# picr22-team-GibiBot-mainboard.net
KiCad netlist of a schematic drawn in Altium Designer
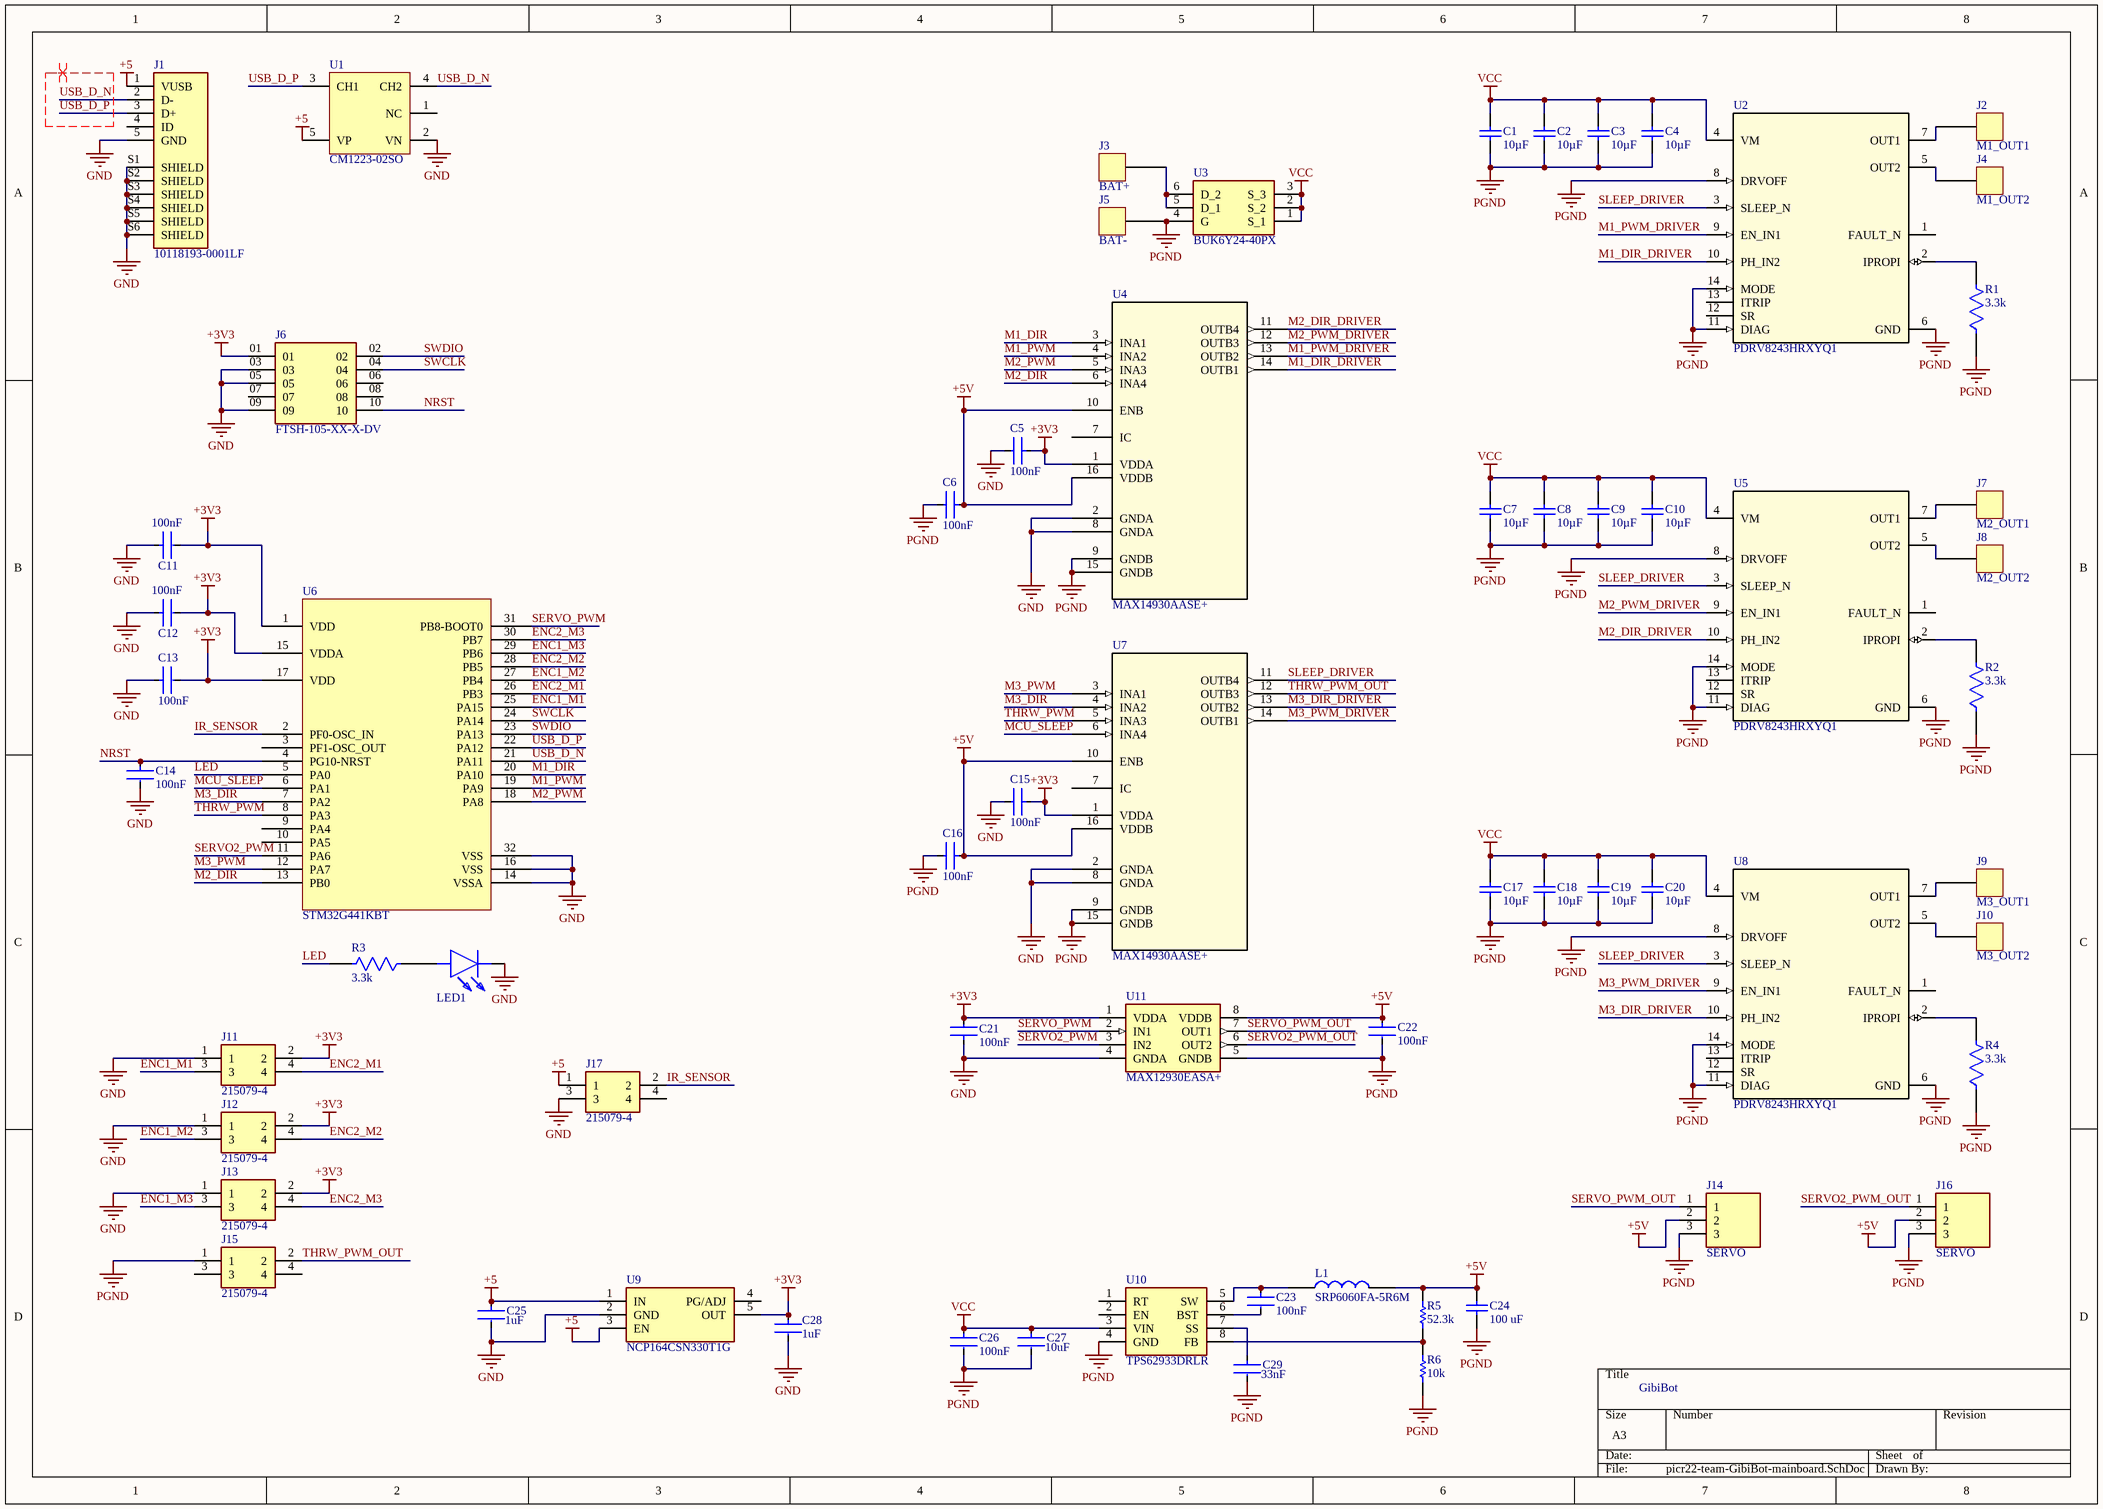
[diagram p0: picr22-team-GibiBot-mainboard.SchDoc]

(export (version "E")
  (design (tool "Eeschema 10.0.6"))
  (components
    (comp (ref "C1")
      (value "GRM21BR61A106KE19L")
      (footprint "MURA-0805_H_1.35_M")
      (description "CAP, Ceramic, 10 uF, 10%, 10 V, 0805, RoHS, Tape and Reel")
      (fields
        (field (name "MANUFACTURER") "Murata")
        (field (name "TOLERANCE") "±10%")
        (field (name "CAPACITANCE") "10µF")
      )
      (libsource (lib "Altium Content Vault") (part "CAP-NP-2"))
    )
    (comp (ref "C2")
      (value "GRM21BR61A106KE19L")
      (footprint "MURA-0805_H_1.35_M")
      (description "CAP, Ceramic, 10 uF, 10%, 10 V, 0805, RoHS, Tape and Reel")
      (fields
        (field (name "MANUFACTURER") "Murata")
        (field (name "TOLERANCE") "±10%")
        (field (name "CAPACITANCE") "10µF")
      )
      (libsource (lib "Altium Content Vault") (part "CAP-NP-2"))
    )
    (comp (ref "C3")
      (value "GRM21BR61A106KE19L")
      (footprint "MURA-0805_H_1.35_M")
      (description "CAP, Ceramic, 10 uF, 10%, 10 V, 0805, RoHS, Tape and Reel")
      (fields
        (field (name "MANUFACTURER") "Murata")
        (field (name "TOLERANCE") "±10%")
        (field (name "CAPACITANCE") "10µF")
      )
      (libsource (lib "Altium Content Vault") (part "CAP-NP-2"))
    )
    (comp (ref "C4")
      (value "GRM21BR61A106KE19L")
      (footprint "MURA-0805_H_1.35_M")
      (description "CAP, Ceramic, 10 uF, 10%, 10 V, 0805, RoHS, Tape and Reel")
      (fields
        (field (name "MANUFACTURER") "Murata")
        (field (name "TOLERANCE") "±10%")
        (field (name "CAPACITANCE") "10µF")
      )
      (libsource (lib "Altium Content Vault") (part "CAP-NP-2"))
    )
    (comp (ref "C5")
      (value "CGA3E2X7R1H104K080AA")
      (footprint "FP-CGA3E-0_3-0_1-IPC_A")
      (description "Cap Ceramic 100nF 50V X7R 10% Pad SMD 0603 +125°C Automotive T/R")
      (fields
        (field (name "TOLERANCE") "10%")
        (field (name "CAPACITANCE") "100nF")
        (field (name "VOLTAGE") "50V")
      )
      (libsource (lib "Altium Content Vault") (part "b4654b650e69147ec39a6b967a45e02"))
    )
    (comp (ref "C6")
      (value "CGA3E2X7R1H104K080AA")
      (footprint "FP-CGA3E-0_3-0_1-IPC_A")
      (description "Cap Ceramic 100nF 50V X7R 10% Pad SMD 0603 +125°C Automotive T/R")
      (fields
        (field (name "TOLERANCE") "10%")
        (field (name "CAPACITANCE") "100nF")
        (field (name "VOLTAGE") "50V")
      )
      (libsource (lib "Altium Content Vault") (part "b4654b650e69147ec39a6b967a45e02"))
    )
    (comp (ref "C7")
      (value "GRM21BR61A106KE19L")
      (footprint "MURA-0805_H_1.35_M")
      (description "CAP, Ceramic, 10 uF, 10%, 10 V, 0805, RoHS, Tape and Reel")
      (fields
        (field (name "MANUFACTURER") "Murata")
        (field (name "TOLERANCE") "±10%")
        (field (name "CAPACITANCE") "10µF")
      )
      (libsource (lib "Altium Content Vault") (part "CAP-NP-2"))
    )
    (comp (ref "C8")
      (value "GRM21BR61A106KE19L")
      (footprint "MURA-0805_H_1.35_M")
      (description "CAP, Ceramic, 10 uF, 10%, 10 V, 0805, RoHS, Tape and Reel")
      (fields
        (field (name "MANUFACTURER") "Murata")
        (field (name "TOLERANCE") "±10%")
        (field (name "CAPACITANCE") "10µF")
      )
      (libsource (lib "Altium Content Vault") (part "CAP-NP-2"))
    )
    (comp (ref "C9")
      (value "GRM21BR61A106KE19L")
      (footprint "MURA-0805_H_1.35_M")
      (description "CAP, Ceramic, 10 uF, 10%, 10 V, 0805, RoHS, Tape and Reel")
      (fields
        (field (name "MANUFACTURER") "Murata")
        (field (name "TOLERANCE") "±10%")
        (field (name "CAPACITANCE") "10µF")
      )
      (libsource (lib "Altium Content Vault") (part "CAP-NP-2"))
    )
    (comp (ref "C10")
      (value "GRM21BR61A106KE19L")
      (footprint "MURA-0805_H_1.35_M")
      (description "CAP, Ceramic, 10 uF, 10%, 10 V, 0805, RoHS, Tape and Reel")
      (fields
        (field (name "MANUFACTURER") "Murata")
        (field (name "TOLERANCE") "±10%")
        (field (name "CAPACITANCE") "10µF")
      )
      (libsource (lib "Altium Content Vault") (part "CAP-NP-2"))
    )
    (comp (ref "C11")
      (value "CGA3E2X7R1H104K080AA")
      (footprint "FP-CGA3E-0_3-0_1-IPC_A")
      (description "Cap Ceramic 100nF 50V X7R 10% Pad SMD 0603 +125°C Automotive T/R")
      (fields
        (field (name "TOLERANCE") "10%")
        (field (name "CAPACITANCE") "100nF")
        (field (name "VOLTAGE") "50V")
      )
      (libsource (lib "Altium Content Vault") (part "b4654b650e69147ec39a6b967a45e02"))
    )
    (comp (ref "C12")
      (value "CGA3E2X7R1H104K080AA")
      (footprint "FP-CGA3E-0_3-0_1-IPC_A")
      (description "Cap Ceramic 100nF 50V X7R 10% Pad SMD 0603 +125°C Automotive T/R")
      (fields
        (field (name "TOLERANCE") "10%")
        (field (name "CAPACITANCE") "100nF")
        (field (name "VOLTAGE") "50V")
      )
      (libsource (lib "Altium Content Vault") (part "b4654b650e69147ec39a6b967a45e02"))
    )
    (comp (ref "C13")
      (value "CGA3E2X7R1H104K080AA")
      (footprint "FP-CGA3E-0_3-0_1-IPC_A")
      (description "Cap Ceramic 100nF 50V X7R 10% Pad SMD 0603 +125°C Automotive T/R")
      (fields
        (field (name "TOLERANCE") "10%")
        (field (name "CAPACITANCE") "100nF")
        (field (name "VOLTAGE") "50V")
      )
      (libsource (lib "Altium Content Vault") (part "b4654b650e69147ec39a6b967a45e02"))
    )
    (comp (ref "C14")
      (value "CGA3E2X7R1H104K080AA")
      (footprint "FP-CGA3E-0_3-0_1-IPC_A")
      (description "Cap Ceramic 100nF 50V X7R 10% Pad SMD 0603 +125°C Automotive T/R")
      (fields
        (field (name "TOLERANCE") "10%")
        (field (name "CAPACITANCE") "100nF")
        (field (name "VOLTAGE") "50V")
      )
      (libsource (lib "Altium Content Vault") (part "b4654b650e69147ec39a6b967a45e02"))
    )
    (comp (ref "C15")
      (value "CGA3E2X7R1H104K080AA")
      (footprint "FP-CGA3E-0_3-0_1-IPC_A")
      (description "Cap Ceramic 100nF 50V X7R 10% Pad SMD 0603 +125°C Automotive T/R")
      (fields
        (field (name "TOLERANCE") "10%")
        (field (name "CAPACITANCE") "100nF")
        (field (name "VOLTAGE") "50V")
      )
      (libsource (lib "Altium Content Vault") (part "b4654b650e69147ec39a6b967a45e02"))
    )
    (comp (ref "C16")
      (value "CGA3E2X7R1H104K080AA")
      (footprint "FP-CGA3E-0_3-0_1-IPC_A")
      (description "Cap Ceramic 100nF 50V X7R 10% Pad SMD 0603 +125°C Automotive T/R")
      (fields
        (field (name "TOLERANCE") "10%")
        (field (name "CAPACITANCE") "100nF")
        (field (name "VOLTAGE") "50V")
      )
      (libsource (lib "Altium Content Vault") (part "b4654b650e69147ec39a6b967a45e02"))
    )
    (comp (ref "C17")
      (value "GRM21BR61A106KE19L")
      (footprint "MURA-0805_H_1.35_M")
      (description "CAP, Ceramic, 10 uF, 10%, 10 V, 0805, RoHS, Tape and Reel")
      (fields
        (field (name "MANUFACTURER") "Murata")
        (field (name "TOLERANCE") "±10%")
        (field (name "CAPACITANCE") "10µF")
      )
      (libsource (lib "Altium Content Vault") (part "CAP-NP-2"))
    )
    (comp (ref "C18")
      (value "GRM21BR61A106KE19L")
      (footprint "MURA-0805_H_1.35_M")
      (description "CAP, Ceramic, 10 uF, 10%, 10 V, 0805, RoHS, Tape and Reel")
      (fields
        (field (name "MANUFACTURER") "Murata")
        (field (name "TOLERANCE") "±10%")
        (field (name "CAPACITANCE") "10µF")
      )
      (libsource (lib "Altium Content Vault") (part "CAP-NP-2"))
    )
    (comp (ref "C19")
      (value "GRM21BR61A106KE19L")
      (footprint "MURA-0805_H_1.35_M")
      (description "CAP, Ceramic, 10 uF, 10%, 10 V, 0805, RoHS, Tape and Reel")
      (fields
        (field (name "MANUFACTURER") "Murata")
        (field (name "TOLERANCE") "±10%")
        (field (name "CAPACITANCE") "10µF")
      )
      (libsource (lib "Altium Content Vault") (part "CAP-NP-2"))
    )
    (comp (ref "C20")
      (value "GRM21BR61A106KE19L")
      (footprint "MURA-0805_H_1.35_M")
      (description "CAP, Ceramic, 10 uF, 10%, 10 V, 0805, RoHS, Tape and Reel")
      (fields
        (field (name "MANUFACTURER") "Murata")
        (field (name "TOLERANCE") "±10%")
        (field (name "CAPACITANCE") "10µF")
      )
      (libsource (lib "Altium Content Vault") (part "CAP-NP-2"))
    )
    (comp (ref "C21")
      (value "CGA3E2X7R1H104K080AA")
      (footprint "FP-CGA3E-0_3-0_1-IPC_A")
      (description "Cap Ceramic 100nF 50V X7R 10% Pad SMD 0603 +125°C Automotive T/R")
      (fields
        (field (name "TOLERANCE") "10%")
        (field (name "CAPACITANCE") "100nF")
        (field (name "VOLTAGE") "50V")
      )
      (libsource (lib "Altium Content Vault") (part "b4654b650e69147ec39a6b967a45e02"))
    )
    (comp (ref "C22")
      (value "CGA3E2X7R1H104K080AA")
      (footprint "FP-CGA3E-0_3-0_1-IPC_A")
      (description "Cap Ceramic 100nF 50V X7R 10% Pad SMD 0603 +125°C Automotive T/R")
      (fields
        (field (name "TOLERANCE") "10%")
        (field (name "CAPACITANCE") "100nF")
        (field (name "VOLTAGE") "50V")
      )
      (libsource (lib "Altium Content Vault") (part "b4654b650e69147ec39a6b967a45e02"))
    )
    (comp (ref "C23")
      (value "CGA3E2X7R1H104K080AA")
      (footprint "FP-CGA3E-0_3-0_1-IPC_A")
      (description "Cap Ceramic 100nF 50V X7R 10% Pad SMD 0603 +125°C Automotive T/R")
      (fields
        (field (name "TOLERANCE") "10%")
        (field (name "CAPACITANCE") "100nF")
        (field (name "VOLTAGE") "50V")
      )
      (libsource (lib "Altium Content Vault") (part "b4654b650e69147ec39a6b967a45e02"))
    )
    (comp (ref "C24")
      (value "GRM31CR60J107ME39L")
      (footprint "CAPC3216X190X55ML30T25")
      (description "Chip Capacitor, 100 uF, +/- 20%, 6.3 V, -55 to 85 degC, 1206 (3216 Metric), RoHS, Tape and Reel")
      (fields (field (name "TOLERANCE") "20%") (field (name "CAPACITANCE") "100 uF"))
      (libsource (lib "Altium Content Vault") (part "CAP-NP-2"))
    )
    (comp (ref "C25")
      (value "C1608X5R1C105K080AA")
      (footprint "FP-C1608-080-0_1-MFG")
      (description "Multilayer Ceramic Capacitors 1μF ±10% 16V X5R SMD 0603")
      (fields
        (field (name "CAPACITANCE") "1uF")
        (field (name "VOLTAGE") "16V")
        (field (name "TOLERANCE") "10%")
      )
      (libsource (lib "Altium Content Vault") (part "236180d848d6139a670b325ea6854c9"))
    )
    (comp (ref "C26")
      (value "CGA3E2X7R1H104K080AA")
      (footprint "FP-CGA3E-0_3-0_1-IPC_A")
      (description "Cap Ceramic 100nF 50V X7R 10% Pad SMD 0603 +125°C Automotive T/R")
      (fields
        (field (name "TOLERANCE") "10%")
        (field (name "CAPACITANCE") "100nF")
        (field (name "VOLTAGE") "50V")
      )
      (libsource (lib "Altium Content Vault") (part "b4654b650e69147ec39a6b967a45e02"))
    )
    (comp (ref "C27")
      (value "C3216X7R1V106M160AC")
      (footprint "FP-C3216-160-0_2-IPC_C")
      (description "Multilayer Ceramic Capacitors 10uF ±20% 35V X7R SMD 1206")
      (fields (field (name "TOLERANCE") "20%") (field (name "CAPACITANCE") "10uF"))
      (libsource (lib "Altium Content Vault") (part "11868f565c42a9108669ba33697ecf6"))
    )
    (comp (ref "C28")
      (value "C1608X5R1C105K080AA")
      (footprint "FP-C1608-080-0_1-MFG")
      (description "Multilayer Ceramic Capacitors 1μF ±10% 16V X5R SMD 0603")
      (fields
        (field (name "CAPACITANCE") "1uF")
        (field (name "VOLTAGE") "16V")
        (field (name "TOLERANCE") "10%")
      )
      (libsource (lib "Altium Content Vault") (part "236180d848d6139a670b325ea6854c9"))
    )
    (comp (ref "C29")
      (value "CL10B333KB8NNNC")
      (footprint "FP-CL10-IPC_B")
      (description "Cap Ceramic 33nF 50V X7R ±10% Pad SMD 0603 +125°C T/R")
      (fields
        (field (name "CAPACITANCE") "33nF")
        (field (name "VOLTAGE") "50V")
        (field (name "TOLERANCE") "10%")
      )
      (libsource (lib "Altium Content Vault") (part "b4654b650e69147ec39a6b967a45e02"))
    )
    (comp (ref "J1")
      (value "10118193-0001LF")
      (footprint "picr22-team-GibiBot-mainboard:FCI_10118193-0001LF")
      (description "USB - micro B USB 2.0 Receptacle Connector 5 Position Surface Mount, Right Angle; Through Hole")
      (fields (field (name "MF") "Amphenol ICC"))
      (libsource (lib "picr22-team-GibiBot-mainboard") (part "10118193-0001LF"))
    )
    (comp (ref "J2")
      (value "M1_OUT1")
      (footprint "Power pad")
      (libsource (lib "picr22-team-GibiBot-mainboard") (part "Power pad"))
    )
    (comp (ref "J3") (value "BAT+") (footprint "Power pad") (libsource (lib "") (part "Power pad_1")))
    (comp (ref "J4")
      (value "M1_OUT2")
      (footprint "Power pad")
      (libsource (lib "picr22-team-GibiBot-mainboard") (part "Power pad"))
    )
    (comp (ref "J5") (value "BAT-") (footprint "Power pad") (libsource (lib "") (part "Power pad_1")))
    (comp (ref "J6")
      (value "FTSH-105-XX-X-DV")
      (footprint "picr22-team-GibiBot-mainboard:SAMTEC_FTSH-105-XX-X-DV")
      (description "Connector Header Surface Mount 10 position 0.050\" (1.27mm)")
      (libsource (lib "picr22-team-GibiBot-mainboard") (part "FTSH-105-XX-X-DV"))
    )
    (comp (ref "J7")
      (value "M2_OUT1")
      (footprint "Power pad")
      (libsource (lib "picr22-team-GibiBot-mainboard") (part "Power pad"))
    )
    (comp (ref "J8")
      (value "M2_OUT2")
      (footprint "Power pad")
      (libsource (lib "picr22-team-GibiBot-mainboard") (part "Power pad"))
    )
    (comp (ref "J9")
      (value "M3_OUT1")
      (footprint "Power pad")
      (libsource (lib "picr22-team-GibiBot-mainboard") (part "Power pad"))
    )
    (comp (ref "J10")
      (value "M3_OUT2")
      (footprint "Power pad")
      (libsource (lib "picr22-team-GibiBot-mainboard") (part "Power pad"))
    )
    (comp (ref "J11")
      (value "215079-4")
      (footprint "TE_215079-4")
      (description "4 Position Receptacle Connector Through Hole")
      (fields (field (name "MF") "TE Connectivity"))
      (libsource (lib "215079-4") (part "215079-4"))
    )
    (comp (ref "J12")
      (value "215079-4")
      (footprint "TE_215079-4")
      (description "4 Position Receptacle Connector Through Hole")
      (fields (field (name "MF") "TE Connectivity"))
      (libsource (lib "215079-4") (part "215079-4"))
    )
    (comp (ref "J13")
      (value "215079-4")
      (footprint "TE_215079-4")
      (description "4 Position Receptacle Connector Through Hole")
      (fields (field (name "MF") "TE Connectivity"))
      (libsource (lib "215079-4") (part "215079-4"))
    )
    (comp (ref "J14")
      (value "SERVO")
      (footprint "picr22-team-GibiBot-mainboard:SERVO")
      (description "Connector")
      (fields
        (field (name "MOUSER PART NUMBER") "649-78208-103")
        (field (name "ARROW PART NUMBER") "78208-103")
      )
      (libsource (lib "picr22-team-GibiBot-mainboard") (part "SERVO"))
    )
    (comp (ref "J15")
      (value "215079-4")
      (footprint "TE_215079-4")
      (description "4 Position Receptacle Connector Through Hole")
      (fields (field (name "MF") "TE Connectivity"))
      (libsource (lib "215079-4") (part "215079-4"))
    )
    (comp (ref "J16")
      (value "SERVO")
      (footprint "picr22-team-GibiBot-mainboard:SERVO")
      (description "Connector")
      (fields
        (field (name "MOUSER PART NUMBER") "649-78208-103")
        (field (name "ARROW PART NUMBER") "78208-103")
      )
      (libsource (lib "picr22-team-GibiBot-mainboard") (part "SERVO"))
    )
    (comp (ref "J17")
      (value "215079-4")
      (footprint "TE_215079-4")
      (description "4 Position Receptacle Connector Through Hole")
      (fields (field (name "MF") "TE Connectivity"))
      (libsource (lib "215079-4") (part "215079-4"))
    )
    (comp (ref "L1")
      (value "SRP6060FA-5R6M")
      (footprint "SRP6060FA5R6M")
      (libsource (lib "picr22-team-GibiBot-mainboard") (part "SRP6060FA-5R6M"))
    )
    (comp (ref "LED1")
      (value "150060SS75000")
      (footprint "SamacSys:LEDC1608X80N")
      (description "LED")
      (fields (field (name "MOUSER PART NUMBER") "710-150060SS75000"))
      (libsource (lib "*") (part "150060SS75000"))
    )
    (comp (ref "R1")
      (value "CRCW06031M00FKEA")
      (footprint "FP-CRCW0603-e3-MFG")
      (description "RES Thick Film, 1MΩ, 1%, 0.1W, 100ppm/°C, 0603")
      (fields (field (name "RESISTANCE") "3.3k") (field (name "TOLERANCE") "1%"))
      (libsource (lib "Altium Content Vault") (part "1029c3af85768c4190bb7ad29bc67b5"))
    )
    (comp (ref "R2")
      (value "CRCW06031M00FKEA")
      (footprint "FP-CRCW0603-e3-MFG")
      (description "RES Thick Film, 1MΩ, 1%, 0.1W, 100ppm/°C, 0603")
      (fields (field (name "RESISTANCE") "3.3k") (field (name "TOLERANCE") "1%"))
      (libsource (lib "Altium Content Vault") (part "1029c3af85768c4190bb7ad29bc67b5"))
    )
    (comp (ref "R3")
      (value "CRCW06031M00FKEA")
      (footprint "FP-CRCW0603-e3-MFG")
      (description "RES Thick Film, 1MΩ, 1%, 0.1W, 100ppm/°C, 0603")
      (fields (field (name "RESISTANCE") "3.3k") (field (name "TOLERANCE") "1%"))
      (libsource (lib "Altium Content Vault") (part "1029c3af85768c4190bb7ad29bc67b5"))
    )
    (comp (ref "R4")
      (value "CRCW06031M00FKEA")
      (footprint "FP-CRCW0603-e3-MFG")
      (description "RES Thick Film, 1MΩ, 1%, 0.1W, 100ppm/°C, 0603")
      (fields (field (name "RESISTANCE") "3.3k") (field (name "TOLERANCE") "1%"))
      (libsource (lib "Altium Content Vault") (part "1029c3af85768c4190bb7ad29bc67b5"))
    )
    (comp (ref "R5")
      (value "RC0603FR-0752K3L")
      (footprint "RESC1608X55X25LL10T15")
      (fields (field (name "MANUFACTURER") "Yageo") (field (name "RESISTANCE") "52.3k"))
      (libsource (lib "Altium Content Vault") (part "RES"))
    )
    (comp (ref "R6")
      (value "CRCW060310K0FKEA")
      (footprint "RESC1609X50X30NL8T20")
      (description "Chip Resistor, 10 KOhm, +/- 1%, 100 mW, -55 to 155 degC, 0603 (1608 Metric), RoHS, Tape and Reel")
      (fields (field (name "MANUFACTURER") "Vishay Semiconductor") (field (name "RESISTANCE") "10k"))
      (libsource (lib "Altium Content Vault") (part "RES-2"))
    )
    (comp (ref "U1")
      (value "CM1223-02SO")
      (footprint "ONSC-SOT23-5-527AH-01_L")
      (fields (field (name "MANUFACTURER") "On Semiconductor"))
      (libsource (lib "Altium Content Vault") (part "ONSC-CM1223-SOT-23-5-527AH-01"))
    )
    (comp (ref "U2")
      (value "PDRV8243HRXYQ1")
      (footprint "RXY0014A-MFG")
      (description "No Description Available")
      (fields (field (name "COPYRIGHT") "Copyright (C) 2022 Ultra Librarian. All rights reserved."))
      (libsource (lib "PDRV8243HRXYQ1") (part "PDRV8243HRXYQ1"))
    )
    (comp (ref "U3")
      (value "BUK6Y24-40PX")
      (footprint "SamacSys:BUK6Y2440PX")
      (description "MOSFET (P-Channel)")
      (fields (field (name "MOUSER PART NUMBER") "771-BUK6Y24-40PX"))
      (libsource (lib "*") (part "BUK6Y24-40PX"))
    )
    (comp (ref "U4")
      (value "MAX14930AASE+")
      (footprint "21-0041_S16+1_MXM")
      (description "No Description Available")
      (fields (field (name "COPYRIGHT") "Copyright (C) 2022 Ultra Librarian. All rights reserved."))
      (libsource (lib "MAX14930AASE&plus_") (part "MAX14930AASE+"))
    )
    (comp (ref "U5")
      (value "PDRV8243HRXYQ1")
      (footprint "RXY0014A-MFG")
      (description "No Description Available")
      (fields (field (name "COPYRIGHT") "Copyright (C) 2022 Ultra Librarian. All rights reserved."))
      (libsource (lib "PDRV8243HRXYQ1") (part "PDRV8243HRXYQ1"))
    )
    (comp (ref "U6")
      (value "STM32G441KBT")
      (footprint "STM32G441KB")
      (libsource (lib "picr22-team-GibiBot-mainboard") (part "STM32G441xB"))
    )
    (comp (ref "U7")
      (value "MAX14930AASE+")
      (footprint "21-0041_S16+1_MXM")
      (description "No Description Available")
      (fields (field (name "COPYRIGHT") "Copyright (C) 2022 Ultra Librarian. All rights reserved."))
      (libsource (lib "MAX14930AASE&plus_") (part "MAX14930AASE+"))
    )
    (comp (ref "U8")
      (value "PDRV8243HRXYQ1")
      (footprint "RXY0014A-MFG")
      (description "No Description Available")
      (fields (field (name "COPYRIGHT") "Copyright (C) 2022 Ultra Librarian. All rights reserved."))
      (libsource (lib "PDRV8243HRXYQ1") (part "PDRV8243HRXYQ1"))
    )
    (comp (ref "U9")
      (value "NCP164CSN330T1G")
      (footprint "SamacSys:SOT95P275X110-5N")
      (description "Integrated Circuit")
      (fields (field (name "MOUSER PART NUMBER") "863-NCP164CSN330T1G"))
      (libsource (lib "*") (part "NCP164CSN330T1G"))
    )
    (comp (ref "U10")
      (value "TPS62933DRLR")
      (footprint "SamacSys:SOTFL50P160X60-8N")
      (description "Integrated Circuit")
      (fields (field (name "MOUSER PART NUMBER") "595-TPS62933DRLR"))
      (libsource (lib "*") (part "TPS62933DRLR"))
    )
    (comp (ref "U11")
      (value "MAX12930EASA+")
      (footprint "SamacSys:SOIC127P600X175-8N")
      (description "Integrated Circuit")
      (fields (field (name "MOUSER PART NUMBER") "700-MAX12930EASA+"))
      (libsource (lib "*") (part "MAX12930EASA+"))
    )
  )
  (nets
    (net (code "1") (name "+3V3") (class "Default")
      (node (ref "C11") (pin "2") (pinfunction "2_2") (pintype "passive"))
      (node (ref "C12") (pin "2") (pinfunction "2_2") (pintype "passive"))
      (node (ref "C13") (pin "2") (pinfunction "2_2") (pintype "passive"))
      (node (ref "C15") (pin "1") (pinfunction "1_1") (pintype "passive"))
      (node (ref "C21") (pin "2") (pinfunction "2_2") (pintype "passive"))
      (node (ref "C28") (pin "2") (pinfunction "2_2") (pintype "passive"))
      (node (ref "C5") (pin "1") (pinfunction "1_1") (pintype "passive"))
      (node (ref "J11") (pin "2") (pinfunction "2_2") (pintype "passive"))
      (node (ref "J12") (pin "2") (pinfunction "2_2") (pintype "passive"))
      (node (ref "J13") (pin "2") (pinfunction "2_2") (pintype "passive"))
      (node (ref "J6") (pin "01") (pinfunction "01_01") (pintype "passive"))
      (node (ref "U11") (pin "1") (pinfunction "VDDA_1") (pintype "power_in"))
      (node (ref "U4") (pin "1") (pinfunction "VDDA_1") (pintype "power_in"))
      (node (ref "U6") (pin "1") (pinfunction "VDD_1") (pintype "passive"))
      (node (ref "U6") (pin "15") (pinfunction "VDDA_15") (pintype "passive"))
      (node (ref "U6") (pin "17") (pinfunction "VDD_17") (pintype "passive"))
      (node (ref "U7") (pin "1") (pinfunction "VDDA_1") (pintype "power_in"))
      (node (ref "U9") (pin "5") (pinfunction "OUT_5") (pintype "passive"))
    )
    (net (code "2") (name "+5") (class "Default")
      (node (ref "C25") (pin "2") (pinfunction "2_2") (pintype "passive"))
      (node (ref "J1") (pin "1") (pinfunction "VUSB_1") (pintype "passive"))
      (node (ref "J17") (pin "1") (pinfunction "1_1") (pintype "passive"))
      (node (ref "U1") (pin "5") (pinfunction "VP_5") (pintype "power_in"))
      (node (ref "U9") (pin "1") (pinfunction "IN_1") (pintype "passive"))
      (node (ref "U9") (pin "3") (pinfunction "EN_3") (pintype "passive"))
    )
    (net (code "3") (name "+5V") (class "Default")
      (node (ref "C16") (pin "1") (pinfunction "1_1") (pintype "passive"))
      (node (ref "C22") (pin "1") (pinfunction "1_1") (pintype "passive"))
      (node (ref "C24") (pin "2") (pinfunction "2_2") (pintype "passive"))
      (node (ref "C6") (pin "1") (pinfunction "1_1") (pintype "passive"))
      (node (ref "J14") (pin "2") (pinfunction "2_2") (pintype "passive"))
      (node (ref "J16") (pin "2") (pinfunction "2_2") (pintype "passive"))
      (node (ref "L1") (pin "2") (pinfunction "2_2") (pintype "passive"))
      (node (ref "R5") (pin "2") (pinfunction "2_2") (pintype "passive"))
      (node (ref "U11") (pin "8") (pinfunction "VDDB_8") (pintype "power_in"))
      (node (ref "U4") (pin "10") (pinfunction "ENB_10") (pintype "passive"))
      (node (ref "U4") (pin "16") (pinfunction "VDDB_16") (pintype "power_in"))
      (node (ref "U7") (pin "10") (pinfunction "ENB_10") (pintype "passive"))
      (node (ref "U7") (pin "16") (pinfunction "VDDB_16") (pintype "power_in"))
    )
    (net (code "4") (name "/ENC1_M1") (class "Default")
      (node (ref "J11") (pin "3") (pinfunction "3_3") (pintype "passive"))
      (node (ref "U6") (pin "25") (pinfunction "PA15_25") (pintype "passive"))
    )
    (net (code "5") (name "/ENC1_M2") (class "Default")
      (node (ref "J12") (pin "3") (pinfunction "3_3") (pintype "passive"))
      (node (ref "U6") (pin "27") (pinfunction "PB4_27") (pintype "passive"))
    )
    (net (code "6") (name "/ENC1_M3") (class "Default")
      (node (ref "J13") (pin "3") (pinfunction "3_3") (pintype "passive"))
      (node (ref "U6") (pin "29") (pinfunction "PB6_29") (pintype "passive"))
    )
    (net (code "7") (name "/ENC2_M1") (class "Default")
      (node (ref "J11") (pin "4") (pinfunction "4_4") (pintype "passive"))
      (node (ref "U6") (pin "26") (pinfunction "PB3_26") (pintype "passive"))
    )
    (net (code "8") (name "/ENC2_M2") (class "Default")
      (node (ref "J12") (pin "4") (pinfunction "4_4") (pintype "passive"))
      (node (ref "U6") (pin "28") (pinfunction "PB5_28") (pintype "passive"))
    )
    (net (code "9") (name "/ENC2_M3") (class "Default")
      (node (ref "J13") (pin "4") (pinfunction "4_4") (pintype "passive"))
      (node (ref "U6") (pin "30") (pinfunction "PB7_30") (pintype "passive"))
    )
    (net (code "10") (name "/IR_SENSOR") (class "Default")
      (node (ref "J17") (pin "2") (pinfunction "2_2") (pintype "passive"))
      (node (ref "U6") (pin "2") (pinfunction "PF0-OSC_IN_2") (pintype "passive"))
    )
    (net (code "11") (name "/LED") (class "Default")
      (node (ref "R3") (pin "2") (pinfunction "2_2") (pintype "passive"))
      (node (ref "U6") (pin "5") (pinfunction "PA0_5") (pintype "passive"))
    )
    (net (code "12") (name "/M1_DIR") (class "Default")
      (node (ref "U4") (pin "3") (pinfunction "INA1_3") (pintype "input"))
      (node (ref "U6") (pin "20") (pinfunction "PA10_20") (pintype "passive"))
    )
    (net (code "13") (name "/M1_DIR_DRIVER") (class "Default")
      (node (ref "U2") (pin "10") (pinfunction "PH_IN2_10") (pintype "input"))
      (node (ref "U4") (pin "14") (pinfunction "OUTB1_14") (pintype "output"))
    )
    (net (code "14") (name "/M1_PWM") (class "Default")
      (node (ref "U4") (pin "4") (pinfunction "INA2_4") (pintype "input"))
      (node (ref "U6") (pin "19") (pinfunction "PA9_19") (pintype "passive"))
    )
    (net (code "15") (name "/M1_PWM_DRIVER") (class "Default")
      (node (ref "U2") (pin "9") (pinfunction "EN_IN1_9") (pintype "input"))
      (node (ref "U4") (pin "13") (pinfunction "OUTB2_13") (pintype "output"))
    )
    (net (code "16") (name "/M2_DIR") (class "Default")
      (node (ref "U4") (pin "6") (pinfunction "INA4_6") (pintype "input"))
      (node (ref "U6") (pin "13") (pinfunction "PB0_13") (pintype "passive"))
    )
    (net (code "17") (name "/M2_DIR_DRIVER") (class "Default")
      (node (ref "U4") (pin "11") (pinfunction "OUTB4_11") (pintype "output"))
      (node (ref "U5") (pin "10") (pinfunction "PH_IN2_10") (pintype "input"))
    )
    (net (code "18") (name "/M2_PWM") (class "Default")
      (node (ref "U4") (pin "5") (pinfunction "INA3_5") (pintype "input"))
      (node (ref "U6") (pin "18") (pinfunction "PA8_18") (pintype "passive"))
    )
    (net (code "19") (name "/M2_PWM_DRIVER") (class "Default")
      (node (ref "U4") (pin "12") (pinfunction "OUTB3_12") (pintype "output"))
      (node (ref "U5") (pin "9") (pinfunction "EN_IN1_9") (pintype "input"))
    )
    (net (code "20") (name "/M3_DIR") (class "Default")
      (node (ref "U6") (pin "7") (pinfunction "PA2_7") (pintype "passive"))
      (node (ref "U7") (pin "4") (pinfunction "INA2_4") (pintype "input"))
    )
    (net (code "21") (name "/M3_DIR_DRIVER") (class "Default")
      (node (ref "U7") (pin "13") (pinfunction "OUTB2_13") (pintype "output"))
      (node (ref "U8") (pin "10") (pinfunction "PH_IN2_10") (pintype "input"))
    )
    (net (code "22") (name "/M3_PWM") (class "Default")
      (node (ref "U6") (pin "12") (pinfunction "PA7_12") (pintype "passive"))
      (node (ref "U7") (pin "3") (pinfunction "INA1_3") (pintype "input"))
    )
    (net (code "23") (name "/M3_PWM_DRIVER") (class "Default")
      (node (ref "U7") (pin "14") (pinfunction "OUTB1_14") (pintype "output"))
      (node (ref "U8") (pin "9") (pinfunction "EN_IN1_9") (pintype "input"))
    )
    (net (code "24") (name "/MCU_SLEEP") (class "Default")
      (node (ref "U6") (pin "6") (pinfunction "PA1_6") (pintype "passive"))
      (node (ref "U7") (pin "6") (pinfunction "INA4_6") (pintype "input"))
    )
    (net (code "25") (name "/NRST") (class "Default")
      (node (ref "C14") (pin "1") (pinfunction "1_1") (pintype "passive"))
      (node (ref "J6") (pin "10") (pinfunction "10_10") (pintype "passive"))
      (node (ref "U6") (pin "4") (pinfunction "PG10-NRST_4") (pintype "passive"))
    )
    (net (code "26") (name "/SERVO2_PWM") (class "Default")
      (node (ref "U11") (pin "3") (pinfunction "IN2_3") (pintype "passive"))
      (node (ref "U6") (pin "11") (pinfunction "PA6_11") (pintype "passive"))
    )
    (net (code "27") (name "/SERVO2_PWM_OUT") (class "Default")
      (node (ref "J16") (pin "1") (pinfunction "1_1") (pintype "passive"))
      (node (ref "U11") (pin "6") (pinfunction "OUT2_6") (pintype "output"))
    )
    (net (code "28") (name "/SERVO_PWM") (class "Default")
      (node (ref "U11") (pin "2") (pinfunction "IN1_2") (pintype "input"))
      (node (ref "U6") (pin "31") (pinfunction "PB8-BOOT0_31") (pintype "passive"))
    )
    (net (code "29") (name "/SERVO_PWM_OUT") (class "Default")
      (node (ref "J14") (pin "1") (pinfunction "1_1") (pintype "passive"))
      (node (ref "U11") (pin "7") (pinfunction "OUT1_7") (pintype "output"))
    )
    (net (code "30") (name "/SLEEP_DRIVER") (class "Default")
      (node (ref "U2") (pin "3") (pinfunction "SLEEP_N_3") (pintype "input"))
      (node (ref "U5") (pin "3") (pinfunction "SLEEP_N_3") (pintype "input"))
      (node (ref "U7") (pin "11") (pinfunction "OUTB4_11") (pintype "output"))
      (node (ref "U8") (pin "3") (pinfunction "SLEEP_N_3") (pintype "input"))
    )
    (net (code "31") (name "/SWCLK") (class "Default")
      (node (ref "J6") (pin "04") (pinfunction "04_04") (pintype "passive"))
      (node (ref "U6") (pin "24") (pinfunction "PA14_24") (pintype "passive"))
    )
    (net (code "32") (name "/SWDIO") (class "Default")
      (node (ref "J6") (pin "02") (pinfunction "02_02") (pintype "passive"))
      (node (ref "U6") (pin "23") (pinfunction "PA13_23") (pintype "passive"))
    )
    (net (code "33") (name "/THRW_PWM") (class "Default")
      (node (ref "U6") (pin "8") (pinfunction "PA3_8") (pintype "passive"))
      (node (ref "U7") (pin "5") (pinfunction "INA3_5") (pintype "input"))
    )
    (net (code "34") (name "/THRW_PWM_OUT") (class "Default")
      (node (ref "J15") (pin "2") (pinfunction "2_2") (pintype "passive"))
      (node (ref "U7") (pin "12") (pinfunction "OUTB3_12") (pintype "output"))
    )
    (net (code "35") (name "/USB_D_N") (class "Default")
      (node (ref "J1") (pin "2") (pinfunction "D-_2") (pintype "passive"))
      (node (ref "U1") (pin "4") (pinfunction "CH2_4") (pintype "passive"))
      (node (ref "U6") (pin "21") (pinfunction "PA11_21") (pintype "passive"))
    )
    (net (code "36") (name "/USB_D_P") (class "Default")
      (node (ref "J1") (pin "3") (pinfunction "D+_3") (pintype "passive"))
      (node (ref "U1") (pin "3") (pinfunction "CH1_3") (pintype "passive"))
      (node (ref "U6") (pin "22") (pinfunction "PA12_22") (pintype "passive"))
    )
    (net (code "37") (name "GND") (class "Default")
      (node (ref "C11") (pin "1") (pinfunction "1_1") (pintype "passive"))
      (node (ref "C12") (pin "1") (pinfunction "1_1") (pintype "passive"))
      (node (ref "C13") (pin "1") (pinfunction "1_1") (pintype "passive"))
      (node (ref "C14") (pin "2") (pinfunction "2_2") (pintype "passive"))
      (node (ref "C15") (pin "2") (pinfunction "2_2") (pintype "passive"))
      (node (ref "C21") (pin "1") (pinfunction "1_1") (pintype "passive"))
      (node (ref "C25") (pin "1") (pinfunction "1_1") (pintype "passive"))
      (node (ref "C28") (pin "1") (pinfunction "1_1") (pintype "passive"))
      (node (ref "C5") (pin "2") (pinfunction "2_2") (pintype "passive"))
      (node (ref "J1") (pin "5") (pinfunction "GND_5") (pintype "passive"))
      (node (ref "J1") (pin "S1") (pinfunction "SHIELD_S1") (pintype "passive"))
      (node (ref "J1") (pin "S2") (pinfunction "SHIELD_S2") (pintype "passive"))
      (node (ref "J1") (pin "S3") (pinfunction "SHIELD_S3") (pintype "passive"))
      (node (ref "J1") (pin "S4") (pinfunction "SHIELD_S4") (pintype "passive"))
      (node (ref "J1") (pin "S5") (pinfunction "SHIELD_S5") (pintype "passive"))
      (node (ref "J1") (pin "S6") (pinfunction "SHIELD_S6") (pintype "passive"))
      (node (ref "J11") (pin "1") (pinfunction "1_1") (pintype "passive"))
      (node (ref "J12") (pin "1") (pinfunction "1_1") (pintype "passive"))
      (node (ref "J13") (pin "1") (pinfunction "1_1") (pintype "passive"))
      (node (ref "J17") (pin "3") (pinfunction "3_3") (pintype "passive"))
      (node (ref "J6") (pin "03") (pinfunction "03_03") (pintype "passive"))
      (node (ref "J6") (pin "05") (pinfunction "05_05") (pintype "passive"))
      (node (ref "J6") (pin "09") (pinfunction "09_09") (pintype "passive"))
      (node (ref "LED1") (pin "1") (pinfunction "K_1") (pintype "passive"))
      (node (ref "U1") (pin "2") (pinfunction "VN_2") (pintype "power_in"))
      (node (ref "U11") (pin "4") (pinfunction "GNDA_4") (pintype "power_in"))
      (node (ref "U4") (pin "2") (pinfunction "GNDA_2") (pintype "power_in"))
      (node (ref "U4") (pin "8") (pinfunction "GNDA_8") (pintype "power_in"))
      (node (ref "U6") (pin "14") (pinfunction "VSSA_14") (pintype "passive"))
      (node (ref "U6") (pin "16") (pinfunction "VSS_16") (pintype "passive"))
      (node (ref "U6") (pin "32") (pinfunction "VSS_32") (pintype "passive"))
      (node (ref "U7") (pin "2") (pinfunction "GNDA_2") (pintype "power_in"))
      (node (ref "U7") (pin "8") (pinfunction "GNDA_8") (pintype "power_in"))
      (node (ref "U9") (pin "2") (pinfunction "GND_2") (pintype "passive"))
    )
    (net (code "38") (name "Net-(J2-PAD)") (class "Default")
      (node (ref "J2") (pin "2") (pinfunction "PAD_2") (pintype "power_in"))
      (node (ref "U2") (pin "7") (pinfunction "OUT1_7") (pintype "passive"))
    )
    (net (code "39") (name "Net-(J3-PAD)") (class "Default")
      (node (ref "J3") (pin "2") (pinfunction "PAD_2") (pintype "power_in"))
      (node (ref "U3") (pin "5") (pinfunction "D_1_5") (pintype "passive"))
      (node (ref "U3") (pin "6") (pinfunction "D_2_6") (pintype "passive"))
    )
    (net (code "40") (name "Net-(J4-PAD)") (class "Default")
      (node (ref "J4") (pin "2") (pinfunction "PAD_2") (pintype "power_in"))
      (node (ref "U2") (pin "5") (pinfunction "OUT2_5") (pintype "passive"))
    )
    (net (code "41") (name "Net-(J7-PAD)") (class "Default")
      (node (ref "J7") (pin "2") (pinfunction "PAD_2") (pintype "power_in"))
      (node (ref "U5") (pin "7") (pinfunction "OUT1_7") (pintype "passive"))
    )
    (net (code "42") (name "Net-(J8-PAD)") (class "Default")
      (node (ref "J8") (pin "2") (pinfunction "PAD_2") (pintype "power_in"))
      (node (ref "U5") (pin "5") (pinfunction "OUT2_5") (pintype "passive"))
    )
    (net (code "43") (name "Net-(J9-PAD)") (class "Default")
      (node (ref "J9") (pin "2") (pinfunction "PAD_2") (pintype "power_in"))
      (node (ref "U8") (pin "7") (pinfunction "OUT1_7") (pintype "passive"))
    )
    (net (code "44") (name "Net-(J10-PAD)") (class "Default")
      (node (ref "J10") (pin "2") (pinfunction "PAD_2") (pintype "power_in"))
      (node (ref "U8") (pin "5") (pinfunction "OUT2_5") (pintype "passive"))
    )
    (net (code "45") (name "Net-(LED1-A)") (class "Default")
      (node (ref "LED1") (pin "2") (pinfunction "A_2") (pintype "passive"))
      (node (ref "R3") (pin "1") (pinfunction "1_1") (pintype "passive"))
    )
    (net (code "46") (name "Net-(U2-IPROPI)") (class "Default")
      (node (ref "R1") (pin "2") (pinfunction "2_2") (pintype "passive"))
      (node (ref "U2") (pin "2") (pinfunction "IPROPI_2") (pintype "bidirectional"))
    )
    (net (code "47") (name "Net-(U5-IPROPI)") (class "Default")
      (node (ref "R2") (pin "2") (pinfunction "2_2") (pintype "passive"))
      (node (ref "U5") (pin "2") (pinfunction "IPROPI_2") (pintype "bidirectional"))
    )
    (net (code "48") (name "Net-(U8-IPROPI)") (class "Default")
      (node (ref "R4") (pin "2") (pinfunction "2_2") (pintype "passive"))
      (node (ref "U8") (pin "2") (pinfunction "IPROPI_2") (pintype "bidirectional"))
    )
    (net (code "49") (name "Net-(U10-BST)") (class "Default")
      (node (ref "C23") (pin "2") (pinfunction "2_2") (pintype "passive"))
      (node (ref "U10") (pin "6") (pinfunction "BST_6") (pintype "passive"))
    )
    (net (code "50") (name "Net-(U10-FB)") (class "Default")
      (node (ref "R5") (pin "1") (pinfunction "1_1") (pintype "passive"))
      (node (ref "R6") (pin "2") (pinfunction "2_2") (pintype "passive"))
      (node (ref "U10") (pin "8") (pinfunction "FB_8") (pintype "passive"))
    )
    (net (code "51") (name "Net-(U10-SS)") (class "Default")
      (node (ref "C29") (pin "1") (pinfunction "1_1") (pintype "passive"))
      (node (ref "U10") (pin "7") (pinfunction "SS_7") (pintype "passive"))
    )
    (net (code "52") (name "Net-(U10-SW)") (class "Default")
      (node (ref "C23") (pin "1") (pinfunction "1_1") (pintype "passive"))
      (node (ref "L1") (pin "1") (pinfunction "1_1") (pintype "passive"))
      (node (ref "U10") (pin "5") (pinfunction "SW_5") (pintype "passive"))
    )
    (net (code "53") (name "PGND") (class "Default")
      (node (ref "C1") (pin "1") (pinfunction "1_1") (pintype "passive"))
      (node (ref "C10") (pin "1") (pinfunction "1_1") (pintype "passive"))
      (node (ref "C16") (pin "2") (pinfunction "2_2") (pintype "passive"))
      (node (ref "C17") (pin "1") (pinfunction "1_1") (pintype "passive"))
      (node (ref "C18") (pin "1") (pinfunction "1_1") (pintype "passive"))
      (node (ref "C19") (pin "1") (pinfunction "1_1") (pintype "passive"))
      (node (ref "C2") (pin "1") (pinfunction "1_1") (pintype "passive"))
      (node (ref "C20") (pin "1") (pinfunction "1_1") (pintype "passive"))
      (node (ref "C22") (pin "2") (pinfunction "2_2") (pintype "passive"))
      (node (ref "C24") (pin "1") (pinfunction "1_1") (pintype "passive"))
      (node (ref "C26") (pin "2") (pinfunction "2_2") (pintype "passive"))
      (node (ref "C27") (pin "2") (pinfunction "2_2") (pintype "passive"))
      (node (ref "C29") (pin "2") (pinfunction "2_2") (pintype "passive"))
      (node (ref "C3") (pin "1") (pinfunction "1_1") (pintype "passive"))
      (node (ref "C4") (pin "1") (pinfunction "1_1") (pintype "passive"))
      (node (ref "C6") (pin "2") (pinfunction "2_2") (pintype "passive"))
      (node (ref "C7") (pin "1") (pinfunction "1_1") (pintype "passive"))
      (node (ref "C8") (pin "1") (pinfunction "1_1") (pintype "passive"))
      (node (ref "C9") (pin "1") (pinfunction "1_1") (pintype "passive"))
      (node (ref "J14") (pin "3") (pinfunction "3_3") (pintype "passive"))
      (node (ref "J15") (pin "1") (pinfunction "1_1") (pintype "passive"))
      (node (ref "J16") (pin "3") (pinfunction "3_3") (pintype "passive"))
      (node (ref "J5") (pin "2") (pinfunction "PAD_2") (pintype "power_in"))
      (node (ref "R1") (pin "1") (pinfunction "1_1") (pintype "passive"))
      (node (ref "R2") (pin "1") (pinfunction "1_1") (pintype "passive"))
      (node (ref "R4") (pin "1") (pinfunction "1_1") (pintype "passive"))
      (node (ref "R6") (pin "1") (pinfunction "1_1") (pintype "passive"))
      (node (ref "U10") (pin "4") (pinfunction "GND_4") (pintype "passive"))
      (node (ref "U11") (pin "5") (pinfunction "GNDB_5") (pintype "power_in"))
      (node (ref "U2") (pin "11") (pinfunction "DIAG_11") (pintype "input"))
      (node (ref "U2") (pin "14") (pinfunction "MODE_14") (pintype "input"))
      (node (ref "U2") (pin "6") (pinfunction "GND_6") (pintype "power_in"))
      (node (ref "U2") (pin "8") (pinfunction "DRVOFF_8") (pintype "input"))
      (node (ref "U3") (pin "4") (pinfunction "G_4") (pintype "passive"))
      (node (ref "U4") (pin "15") (pinfunction "GNDB_15") (pintype "power_in"))
      (node (ref "U4") (pin "9") (pinfunction "GNDB_9") (pintype "power_in"))
      (node (ref "U5") (pin "11") (pinfunction "DIAG_11") (pintype "input"))
      (node (ref "U5") (pin "14") (pinfunction "MODE_14") (pintype "input"))
      (node (ref "U5") (pin "6") (pinfunction "GND_6") (pintype "power_in"))
      (node (ref "U5") (pin "8") (pinfunction "DRVOFF_8") (pintype "input"))
      (node (ref "U7") (pin "15") (pinfunction "GNDB_15") (pintype "power_in"))
      (node (ref "U7") (pin "9") (pinfunction "GNDB_9") (pintype "power_in"))
      (node (ref "U8") (pin "11") (pinfunction "DIAG_11") (pintype "input"))
      (node (ref "U8") (pin "14") (pinfunction "MODE_14") (pintype "input"))
      (node (ref "U8") (pin "6") (pinfunction "GND_6") (pintype "power_in"))
      (node (ref "U8") (pin "8") (pinfunction "DRVOFF_8") (pintype "input"))
    )
    (net (code "54") (name "VCC") (class "Default")
      (node (ref "C1") (pin "2") (pinfunction "2_2") (pintype "passive"))
      (node (ref "C10") (pin "2") (pinfunction "2_2") (pintype "passive"))
      (node (ref "C17") (pin "2") (pinfunction "2_2") (pintype "passive"))
      (node (ref "C18") (pin "2") (pinfunction "2_2") (pintype "passive"))
      (node (ref "C19") (pin "2") (pinfunction "2_2") (pintype "passive"))
      (node (ref "C2") (pin "2") (pinfunction "2_2") (pintype "passive"))
      (node (ref "C20") (pin "2") (pinfunction "2_2") (pintype "passive"))
      (node (ref "C26") (pin "1") (pinfunction "1_1") (pintype "passive"))
      (node (ref "C27") (pin "1") (pinfunction "1_1") (pintype "passive"))
      (node (ref "C3") (pin "2") (pinfunction "2_2") (pintype "passive"))
      (node (ref "C4") (pin "2") (pinfunction "2_2") (pintype "passive"))
      (node (ref "C7") (pin "2") (pinfunction "2_2") (pintype "passive"))
      (node (ref "C8") (pin "2") (pinfunction "2_2") (pintype "passive"))
      (node (ref "C9") (pin "2") (pinfunction "2_2") (pintype "passive"))
      (node (ref "U10") (pin "3") (pinfunction "VIN_3") (pintype "passive"))
      (node (ref "U2") (pin "4") (pinfunction "VM_4") (pintype "power_in"))
      (node (ref "U3") (pin "1") (pinfunction "S_1_1") (pintype "passive"))
      (node (ref "U3") (pin "2") (pinfunction "S_2_2") (pintype "passive"))
      (node (ref "U3") (pin "3") (pinfunction "S_3_3") (pintype "passive"))
      (node (ref "U5") (pin "4") (pinfunction "VM_4") (pintype "power_in"))
      (node (ref "U8") (pin "4") (pinfunction "VM_4") (pintype "power_in"))
    )
    (net (code "55") (name "unconnected-(J1-ID-Pad4)") (class "Default")
      (node (ref "J1") (pin "4") (pinfunction "ID_4") (pintype "passive"))
    )
    (net (code "56") (name "unconnected-(J6-Pad06)") (class "Default")
      (node (ref "J6") (pin "06") (pinfunction "06_06") (pintype "passive"))
    )
    (net (code "57") (name "unconnected-(J6-Pad07)") (class "Default")
      (node (ref "J6") (pin "07") (pinfunction "07_07") (pintype "passive"))
    )
    (net (code "58") (name "unconnected-(J6-Pad08)") (class "Default")
      (node (ref "J6") (pin "08") (pinfunction "08_08") (pintype "passive"))
    )
    (net (code "59") (name "unconnected-(J15-Pad3)") (class "Default")
      (node (ref "J15") (pin "3") (pinfunction "3_3") (pintype "passive"))
    )
    (net (code "60") (name "unconnected-(J15-Pad4)") (class "Default")
      (node (ref "J15") (pin "4") (pinfunction "4_4") (pintype "passive"))
    )
    (net (code "61") (name "unconnected-(J17-Pad4)") (class "Default")
      (node (ref "J17") (pin "4") (pinfunction "4_4") (pintype "passive"))
    )
    (net (code "62") (name "unconnected-(U1-NC-Pad1)") (class "Default")
      (node (ref "U1") (pin "1") (pinfunction "NC_1") (pintype "passive"))
    )
    (net (code "63") (name "unconnected-(U2-FAULT_N-Pad1)") (class "Default")
      (node (ref "U2") (pin "1") (pinfunction "FAULT_N_1") (pintype "open_collector"))
    )
    (net (code "64") (name "unconnected-(U2-ITRIP-Pad13)") (class "Default")
      (node (ref "U2") (pin "13") (pinfunction "ITRIP_13") (pintype "passive"))
    )
    (net (code "65") (name "unconnected-(U2-SR-Pad12)") (class "Default")
      (node (ref "U2") (pin "12") (pinfunction "SR_12") (pintype "passive"))
    )
    (net (code "66") (name "unconnected-(U4-IC-Pad7)") (class "Default")
      (node (ref "U4") (pin "7") (pinfunction "IC_7") (pintype "passive"))
    )
    (net (code "67") (name "unconnected-(U5-FAULT_N-Pad1)") (class "Default")
      (node (ref "U5") (pin "1") (pinfunction "FAULT_N_1") (pintype "open_collector"))
    )
    (net (code "68") (name "unconnected-(U5-ITRIP-Pad13)") (class "Default")
      (node (ref "U5") (pin "13") (pinfunction "ITRIP_13") (pintype "passive"))
    )
    (net (code "69") (name "unconnected-(U5-SR-Pad12)") (class "Default")
      (node (ref "U5") (pin "12") (pinfunction "SR_12") (pintype "passive"))
    )
    (net (code "70") (name "unconnected-(U6-PA4-Pad9)") (class "Default")
      (node (ref "U6") (pin "9") (pinfunction "PA4_9") (pintype "passive"))
    )
    (net (code "71") (name "unconnected-(U6-PA5-Pad10)") (class "Default")
      (node (ref "U6") (pin "10") (pinfunction "PA5_10") (pintype "passive"))
    )
    (net (code "72") (name "unconnected-(U6-PF1-OSC_OUT-Pad3)") (class "Default")
      (node (ref "U6") (pin "3") (pinfunction "PF1-OSC_OUT_3") (pintype "passive"))
    )
    (net (code "73") (name "unconnected-(U7-IC-Pad7)") (class "Default")
      (node (ref "U7") (pin "7") (pinfunction "IC_7") (pintype "passive"))
    )
    (net (code "74") (name "unconnected-(U8-FAULT_N-Pad1)") (class "Default")
      (node (ref "U8") (pin "1") (pinfunction "FAULT_N_1") (pintype "open_collector"))
    )
    (net (code "75") (name "unconnected-(U8-ITRIP-Pad13)") (class "Default")
      (node (ref "U8") (pin "13") (pinfunction "ITRIP_13") (pintype "passive"))
    )
    (net (code "76") (name "unconnected-(U8-SR-Pad12)") (class "Default")
      (node (ref "U8") (pin "12") (pinfunction "SR_12") (pintype "passive"))
    )
    (net (code "77") (name "unconnected-(U9-PG{slash}ADJ-Pad4)") (class "Default")
      (node (ref "U9") (pin "4") (pinfunction "PG/ADJ_4") (pintype "passive"))
    )
    (net (code "78") (name "unconnected-(U10-EN-Pad2)") (class "Default")
      (node (ref "U10") (pin "2") (pinfunction "EN_2") (pintype "passive"))
    )
    (net (code "79") (name "unconnected-(U10-RT-Pad1)") (class "Default")
      (node (ref "U10") (pin "1") (pinfunction "RT_1") (pintype "passive"))
    )
  )
)
